# 7_dc_dc_5v_radios.net
KiCad netlist of a schematic drawn in Altium Designer
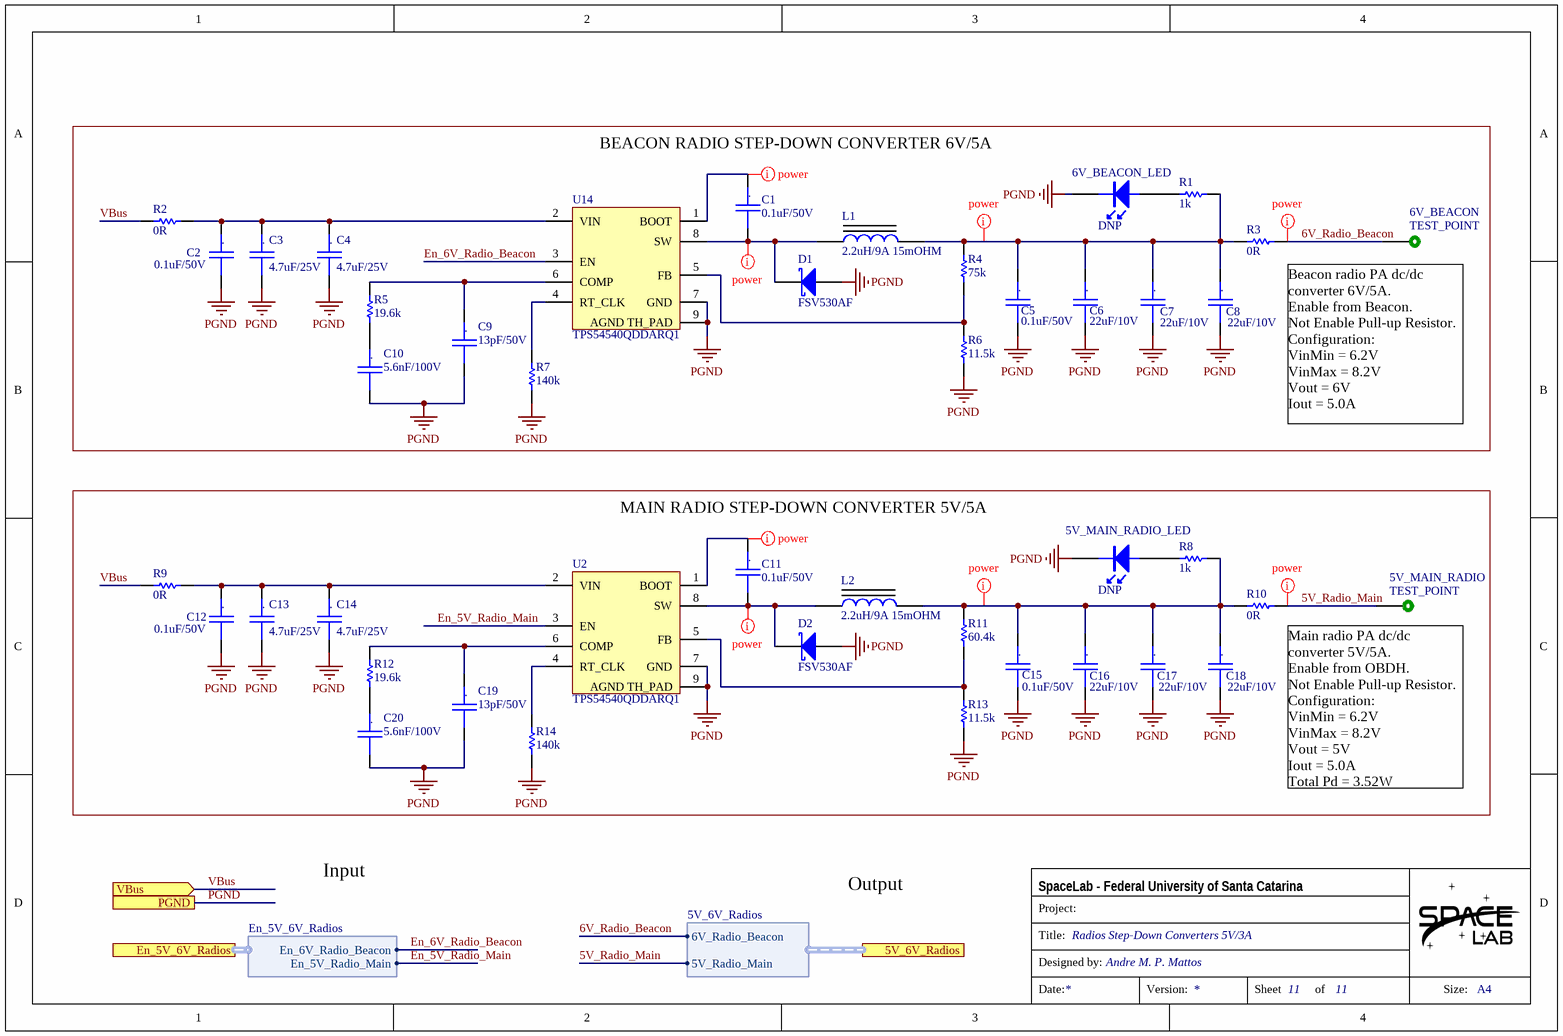
[diagram p0: 7_dc_dc_5v_radios.schdoc]

(export (version "E")
  (design (tool "Eeschema 10.0.6"))
  (components
    (comp (ref "5V_MAIN_RADIO")
      (value "TEST_POINT")
      (footprint "TEST_POINT")
      (description "Test point")
      (libsource (lib "PCB_Project_FlightModel_EPS") (part "TEST_POINT"))
    )
    (comp (ref "5V_MAIN_RADIO_LED")
      (value "DNP")
      (footprint "0603-LED")
      (description "SMD Green LED")
      (fields (field (name "PARTNUMBER") "150060VS75000") (field (name "MANUFACTURER") "Wurth Electronics"))
      (libsource (lib "PCB_Project_FlightModel_EPS") (part "LED/G_0603"))
    )
    (comp (ref "6V_BEACON")
      (value "TEST_POINT")
      (footprint "TEST_POINT")
      (description "Test point")
      (libsource (lib "PCB_Project_FlightModel_EPS") (part "TEST_POINT"))
    )
    (comp (ref "6V_BEACON_LED")
      (value "DNP")
      (footprint "0603-LED")
      (description "SMD Green LED")
      (fields (field (name "PARTNUMBER") "150060VS75000") (field (name "MANUFACTURER") "Wurth Electronics"))
      (libsource (lib "PCB_Project_FlightModel_EPS") (part "LED/G_0603"))
    )
    (comp (ref "C1")
      (value "0.1uF/50V")
      (footprint "CC0805")
      (description "CAP CER 0.1UF 50V 10% X7R 0805")
      (fields (field (name "PARTNUMBER") "CC0805KRX7R9BB104") (field (name "MANUFACTURER") "Yageo"))
      (libsource (lib "PCB_Project_FlightModel_EPS") (part "Cap_Cer_X7R_0.1uF_50V_0805"))
    )
    (comp (ref "C2")
      (value "0.1uF/50V")
      (footprint "CC0805")
      (description "CAP CER 0.1UF 50V 10% X7R 0805")
      (fields (field (name "PARTNUMBER") "CC0805KRX7R9BB104") (field (name "MANUFACTURER") "Yageo"))
      (libsource (lib "PCB_Project_FlightModel_EPS") (part "Cap_Cer_X7R_0.1uF_50V_0805"))
    )
    (comp (ref "C3")
      (value "4.7uF/25V")
      (footprint "CC0805")
      (description "CAP CER 4.7uF 25V 10% X7R 0805")
      (fields (field (name "PARTNUMBER") "CC0805KKX7R8BB475") (field (name "MANUFACTURER") "Yageo"))
      (libsource (lib "PCB_Project_FlightModel_EPS") (part "Cap_Cer_X7R_4.7uF_25V_0805"))
    )
    (comp (ref "C4")
      (value "4.7uF/25V")
      (footprint "CC0805")
      (description "CAP CER 4.7uF 25V 10% X7R 0805")
      (fields (field (name "PARTNUMBER") "CC0805KKX7R8BB475") (field (name "MANUFACTURER") "Yageo"))
      (libsource (lib "PCB_Project_FlightModel_EPS") (part "Cap_Cer_X7R_4.7uF_25V_0805"))
    )
    (comp (ref "C5")
      (value "0.1uF/50V")
      (footprint "CC0805")
      (description "CAP CER 0.1UF 50V 10% X7R 0805")
      (fields (field (name "PARTNUMBER") "CC0805KRX7R9BB104") (field (name "MANUFACTURER") "Yageo"))
      (libsource (lib "PCB_Project_FlightModel_EPS") (part "Cap_Cer_X7R_0.1uF_50V_0805"))
    )
    (comp (ref "C6")
      (value "22uF/10V")
      (footprint "CC1206")
      (description "CAP CER 22uF 10V 10% X7R 1206")
      (fields (field (name "PARTNUMBER") "GRM31CR71A226KE15L") (field (name "MANUFACTURER") "Murata"))
      (libsource (lib "PCB_Project_FlightModel_EPS") (part "Cap_Cer_X7R_22uF_10V_1206"))
    )
    (comp (ref "C7")
      (value "22uF/10V")
      (footprint "CC1206")
      (description "CAP CER 22uF 10V 10% X7R 1206")
      (fields (field (name "PARTNUMBER") "GRM31CR71A226KE15L") (field (name "MANUFACTURER") "Murata"))
      (libsource (lib "PCB_Project_FlightModel_EPS") (part "Cap_Cer_X7R_22uF_10V_1206"))
    )
    (comp (ref "C8")
      (value "22uF/10V")
      (footprint "CC1206")
      (description "CAP CER 22uF 10V 10% X7R 1206")
      (fields (field (name "PARTNUMBER") "GRM31CR71A226KE15L") (field (name "MANUFACTURER") "Murata"))
      (libsource (lib "PCB_Project_FlightModel_EPS") (part "Cap_Cer_X7R_22uF_10V_1206"))
    )
    (comp (ref "C9")
      (value "13pF/50V")
      (footprint "CC0603")
      (description "CAP CER 13PF 50V 0603 NP0")
      (fields (field (name "PARTNUMBER") "C0603C130J5GAC7867") (field (name "MANUFACTURER") "KEMET"))
      (libsource (lib "PCB_Project_FlightModel_EPS") (part "Cap_Cer_C0G_13pF_50V_0603"))
    )
    (comp (ref "C10")
      (value "5.6nF/100V")
      (footprint "CC0603")
      (description "CAP CER 5.6nF 100V 0603")
      (fields (field (name "PARTNUMBER") "C1608C0G2A562J080AE") (field (name "MANUFACTURER") "TDK"))
      (libsource (lib "PCB_Project_FlightModel_EPS") (part "Cap_Cer_C0G_5.6nF_100V_0603"))
    )
    (comp (ref "C11")
      (value "0.1uF/50V")
      (footprint "CC0805")
      (description "CAP CER 0.1UF 50V 10% X7R 0805")
      (fields (field (name "PARTNUMBER") "CC0805KRX7R9BB104") (field (name "MANUFACTURER") "Yageo"))
      (libsource (lib "PCB_Project_FlightModel_EPS") (part "Cap_Cer_X7R_0.1uF_50V_0805"))
    )
    (comp (ref "C12")
      (value "0.1uF/50V")
      (footprint "CC0805")
      (description "CAP CER 0.1UF 50V 10% X7R 0805")
      (fields (field (name "PARTNUMBER") "CC0805KRX7R9BB104") (field (name "MANUFACTURER") "Yageo"))
      (libsource (lib "PCB_Project_FlightModel_EPS") (part "Cap_Cer_X7R_0.1uF_50V_0805"))
    )
    (comp (ref "C13")
      (value "4.7uF/25V")
      (footprint "CC0805")
      (description "CAP CER 4.7uF 25V 10% X7R 0805")
      (fields (field (name "PARTNUMBER") "CC0805KKX7R8BB475") (field (name "MANUFACTURER") "Yageo"))
      (libsource (lib "PCB_Project_FlightModel_EPS") (part "Cap_Cer_X7R_4.7uF_25V_0805"))
    )
    (comp (ref "C14")
      (value "4.7uF/25V")
      (footprint "CC0805")
      (description "CAP CER 4.7uF 25V 10% X7R 0805")
      (fields (field (name "PARTNUMBER") "CC0805KKX7R8BB475") (field (name "MANUFACTURER") "Yageo"))
      (libsource (lib "PCB_Project_FlightModel_EPS") (part "Cap_Cer_X7R_4.7uF_25V_0805"))
    )
    (comp (ref "C15")
      (value "0.1uF/50V")
      (footprint "CC0805")
      (description "CAP CER 0.1UF 50V 10% X7R 0805")
      (fields (field (name "PARTNUMBER") "CC0805KRX7R9BB104") (field (name "MANUFACTURER") "Yageo"))
      (libsource (lib "PCB_Project_FlightModel_EPS") (part "Cap_Cer_X7R_0.1uF_50V_0805"))
    )
    (comp (ref "C16")
      (value "22uF/10V")
      (footprint "CC1206")
      (description "CAP CER 22uF 10V 10% X7R 1206")
      (fields (field (name "PARTNUMBER") "GRM31CR71A226KE15L") (field (name "MANUFACTURER") "Murata"))
      (libsource (lib "PCB_Project_FlightModel_EPS") (part "Cap_Cer_X7R_22uF_10V_1206"))
    )
    (comp (ref "C17")
      (value "22uF/10V")
      (footprint "CC1206")
      (description "CAP CER 22uF 10V 10% X7R 1206")
      (fields (field (name "PARTNUMBER") "GRM31CR71A226KE15L") (field (name "MANUFACTURER") "Murata"))
      (libsource (lib "PCB_Project_FlightModel_EPS") (part "Cap_Cer_X7R_22uF_10V_1206"))
    )
    (comp (ref "C18")
      (value "22uF/10V")
      (footprint "CC1206")
      (description "CAP CER 22uF 10V 10% X7R 1206")
      (fields (field (name "PARTNUMBER") "GRM31CR71A226KE15L") (field (name "MANUFACTURER") "Murata"))
      (libsource (lib "PCB_Project_FlightModel_EPS") (part "Cap_Cer_X7R_22uF_10V_1206"))
    )
    (comp (ref "C19")
      (value "13pF/50V")
      (footprint "CC0603")
      (description "CAP CER 13PF 50V 0603 NP0")
      (fields (field (name "PARTNUMBER") "C0603C130J5GAC7867") (field (name "MANUFACTURER") "KEMET"))
      (libsource (lib "PCB_Project_FlightModel_EPS") (part "Cap_Cer_C0G_13pF_50V_0603"))
    )
    (comp (ref "C20")
      (value "5.6nF/100V")
      (footprint "CC0603")
      (description "CAP CER 5.6nF 100V 0603")
      (fields (field (name "PARTNUMBER") "C1608C0G2A562J080AE") (field (name "MANUFACTURER") "TDK"))
      (libsource (lib "PCB_Project_FlightModel_EPS") (part "Cap_Cer_C0G_5.6nF_100V_0603"))
    )
    (comp (ref "D1")
      (value "FSV530AF")
      (footprint "DO-214AC")
      (description "DIODE SCHOTTKY 30V 5A DO-214AA")
      (fields (field (name "MANUFACTURER") "ON Semiconductor / Fairchild"))
      (libsource (lib "PCB_Project_FlightModel_EPS") (part "DIODE_SCHOTTKY_30V_5A_RB080L-30TE25"))
    )
    (comp (ref "D2")
      (value "FSV530AF")
      (footprint "DO-214AC")
      (description "DIODE SCHOTTKY 30V 5A DO-214AA")
      (fields (field (name "MANUFACTURER") "ON Semiconductor / Fairchild"))
      (libsource (lib "PCB_Project_FlightModel_EPS") (part "DIODE_SCHOTTKY_30V_5A_RB080L-30TE25"))
    )
    (comp (ref "L1")
      (value "2.2uH/9A 15mOHM")
      (footprint "Ind_SRP6540")
      (description "INDUCTOR 2.2UH 9A SMD")
      (fields (field (name "PARTNUMBER") "SRP6540-2R2M") (field (name "MANUFACTURER") "Bourns"))
      (libsource (lib "PCB_Project_FlightModel_EPS") (part "IND_POWER_2.2uH_9A_15mR"))
    )
    (comp (ref "L2")
      (value "2.2uH/9A 15mOHM")
      (footprint "Ind_SRP6540")
      (description "INDUCTOR 2.2UH 9A SMD")
      (fields (field (name "PARTNUMBER") "SRP6540-2R2M") (field (name "MANUFACTURER") "Bourns"))
      (libsource (lib "PCB_Project_FlightModel_EPS") (part "IND_POWER_2.2uH_9A_15mR"))
    )
    (comp (ref "R1")
      (value "1k")
      (footprint "0603")
      (description "RES 1.0K OHM 1/8W 1% 0603")
      (fields (field (name "PARTNUMBER") "MCT06030C1001FP500") (field (name "MANUFACTURER") "Vishay"))
      (libsource (lib "PCB_Project_FlightModel_EPS") (part "R1.0k_1%_1/8W_0603"))
    )
    (comp (ref "R2")
      (value "0R")
      (footprint "1206")
      (description "RES 0.0 OHM 3/4W JUMP 1206")
      (fields
        (field (name "PARTNUMBER") "HCJ1206ZT0R00")
        (field (name "MANUFACTURER") "Stackpole Electronics")
      )
      (libsource (lib "PCB_Project_FlightModel_EPS") (part "R0R_JUMPER_3/4W_1206"))
    )
    (comp (ref "R3")
      (value "0R")
      (footprint "1206")
      (description "RES 0.0 OHM 3/4W JUMP 1206")
      (fields
        (field (name "PARTNUMBER") "HCJ1206ZT0R00")
        (field (name "MANUFACTURER") "Stackpole Electronics")
      )
      (libsource (lib "PCB_Project_FlightModel_EPS") (part "R0R_JUMPER_3/4W_1206"))
    )
    (comp (ref "R4")
      (value "75k")
      (footprint "0805")
      (description "RES 75k OHM 1/8W 1% 0805")
      (fields (field (name "PARTNUMBER") "RMCF0805FT75K0") (field (name "MANUFACTURER") "Panasonic"))
      (libsource (lib "schematics_library_legacy") (part "R75k_1%_1/8W_0805_1"))
    )
    (comp (ref "R5")
      (value "19.6k")
      (footprint "0603")
      (description "RES 19.6k OHM 1/10W 1% 0603")
      (fields (field (name "PARTNUMBER") "ERJ-3EKF1962V") (field (name "MANUFACTURER") "Panasonic"))
      (libsource (lib "PCB_Project_FlightModel_EPS") (part "R19.6k_1%_1/10W_0603"))
    )
    (comp (ref "R6")
      (value "11.5k")
      (footprint "0805")
      (description "RES 11.5k OHM 1/8W 1% 0805")
      (fields (field (name "PARTNUMBER") "AC0805FR-0711K5L") (field (name "MANUFACTURER") "Yageo"))
      (libsource (lib "PCB_Project_FlightModel_EPS") (part "R11.5k_1%_1/8W_0805"))
    )
    (comp (ref "R7")
      (value "140k")
      (footprint "0603")
      (description "RES 140k OHM 1/5W 1% 0603")
      (fields (field (name "PARTNUMBER") "ERJ-P03F1403V") (field (name "MANUFACTURER") "Panasonic"))
      (libsource (lib "PCB_Project_FlightModel_EPS") (part "R140k_1%_1/5W_0603"))
    )
    (comp (ref "R8")
      (value "1k")
      (footprint "0603")
      (description "RES 1.0K OHM 1/8W 1% 0603")
      (fields (field (name "PARTNUMBER") "MCT06030C1001FP500") (field (name "MANUFACTURER") "Vishay"))
      (libsource (lib "PCB_Project_FlightModel_EPS") (part "R1.0k_1%_1/8W_0603"))
    )
    (comp (ref "R9")
      (value "0R")
      (footprint "1206")
      (description "RES 0.0 OHM 3/4W JUMP 1206")
      (fields
        (field (name "PARTNUMBER") "HCJ1206ZT0R00")
        (field (name "MANUFACTURER") "Stackpole Electronics")
      )
      (libsource (lib "PCB_Project_FlightModel_EPS") (part "R0R_JUMPER_3/4W_1206"))
    )
    (comp (ref "R10")
      (value "0R")
      (footprint "1206")
      (description "RES 0.0 OHM 3/4W JUMP 1206")
      (fields
        (field (name "PARTNUMBER") "HCJ1206ZT0R00")
        (field (name "MANUFACTURER") "Stackpole Electronics")
      )
      (libsource (lib "PCB_Project_FlightModel_EPS") (part "R0R_JUMPER_3/4W_1206"))
    )
    (comp (ref "R11")
      (value "60.4k")
      (footprint "0805")
      (description "RES 60.4k OHM 1/8W 1% 0805")
      (fields (field (name "PARTNUMBER") "ERJ-6ENF6042V") (field (name "MANUFACTURER") "Panasonic"))
      (libsource (lib "PCB_Project_FlightModel_EPS") (part "R60.4k_1%_1/8W_0805"))
    )
    (comp (ref "R12")
      (value "19.6k")
      (footprint "0603")
      (description "RES 19.6k OHM 1/10W 1% 0603")
      (fields (field (name "PARTNUMBER") "ERJ-3EKF1962V") (field (name "MANUFACTURER") "Panasonic"))
      (libsource (lib "PCB_Project_FlightModel_EPS") (part "R19.6k_1%_1/10W_0603"))
    )
    (comp (ref "R13")
      (value "11.5k")
      (footprint "0805")
      (description "RES 11.5k OHM 1/8W 1% 0805")
      (fields (field (name "PARTNUMBER") "AC0805FR-0711K5L") (field (name "MANUFACTURER") "Yageo"))
      (libsource (lib "PCB_Project_FlightModel_EPS") (part "R11.5k_1%_1/8W_0805"))
    )
    (comp (ref "R14")
      (value "140k")
      (footprint "0603")
      (description "RES 140k OHM 1/5W 1% 0603")
      (fields (field (name "PARTNUMBER") "ERJ-P03F1403V") (field (name "MANUFACTURER") "Panasonic"))
      (libsource (lib "PCB_Project_FlightModel_EPS") (part "R140k_1%_1/5W_0603"))
    )
    (comp (ref "U2")
      (value "TPS54540QDDARQ1")
      (footprint "SO8 Power PAD")
      (fields (field (name "MANUFACTURER") "Texas Instruments"))
      (libsource (lib "PCB_Project_FlightModel_EPS") (part "TPS54540QDDARQ1"))
    )
    (comp (ref "U14")
      (value "TPS54540QDDARQ1")
      (footprint "SO8 Power PAD")
      (fields (field (name "MANUFACTURER") "Texas Instruments"))
      (libsource (lib "PCB_Project_FlightModel_EPS") (part "TPS54540QDDARQ1"))
    )
  )
  (nets
    (net (code "3") (name "/5V_Radio_Main") (class "Default")
      (node (ref "5V_MAIN_RADIO") (pin "1") (pinfunction "1_1") (pintype "passive"))
      (node (ref "R10") (pin "1") (pinfunction "1_1") (pintype "passive"))
    )
    (net (code "4") (name "/6V_Radio_Beacon") (class "Default")
      (node (ref "6V_BEACON") (pin "1") (pinfunction "1_1") (pintype "passive"))
      (node (ref "R3") (pin "1") (pinfunction "1_1") (pintype "passive"))
    )
    (net (code "5") (name "/En_5V_Radio_Main") (class "Default")
      (node (ref "U2") (pin "3") (pinfunction "EN_3") (pintype "passive"))
    )
    (net (code "6") (name "/En_6V_Radio_Beacon") (class "Default")
      (node (ref "U14") (pin "3") (pinfunction "EN_3") (pintype "passive"))
    )
    (net (code "7") (name "/VBus") (class "Default")
      (node (ref "R2") (pin "2") (pinfunction "2_2") (pintype "passive"))
      (node (ref "R9") (pin "2") (pinfunction "2_2") (pintype "passive"))
    )
    (net (code "10") (name "Net-(5V_MAIN_RADIO_LED-A)") (class "Default")
      (node (ref "5V_MAIN_RADIO_LED") (pin "1") (pinfunction "A_1") (pintype "passive"))
      (node (ref "R8") (pin "2") (pinfunction "2_2") (pintype "passive"))
    )
    (net (code "11") (name "Net-(6V_BEACON_LED-A)") (class "Default")
      (node (ref "6V_BEACON_LED") (pin "1") (pinfunction "A_1") (pintype "passive"))
      (node (ref "R1") (pin "2") (pinfunction "2_2") (pintype "passive"))
    )
    (net (code "12") (name "Net-(C5-Pad1)") (class "Default")
      (node (ref "C5") (pin "1") (pinfunction "1_1") (pintype "passive"))
      (node (ref "C6") (pin "1") (pinfunction "1_1") (pintype "passive"))
      (node (ref "C7") (pin "1") (pinfunction "1_1") (pintype "passive"))
      (node (ref "C8") (pin "1") (pinfunction "1_1") (pintype "passive"))
      (node (ref "L1") (pin "2") (pinfunction "2_2") (pintype "passive"))
      (node (ref "R1") (pin "1") (pinfunction "1_1") (pintype "passive"))
      (node (ref "R3") (pin "2") (pinfunction "2_2") (pintype "passive"))
      (node (ref "R4") (pin "2") (pinfunction "2_2") (pintype "passive"))
    )
    (net (code "13") (name "Net-(C10-Pad1)") (class "Default")
      (node (ref "C10") (pin "1") (pinfunction "1_1") (pintype "passive"))
      (node (ref "R5") (pin "1") (pinfunction "1_1") (pintype "passive"))
    )
    (net (code "14") (name "Net-(C15-Pad1)") (class "Default")
      (node (ref "C15") (pin "1") (pinfunction "1_1") (pintype "passive"))
      (node (ref "C16") (pin "1") (pinfunction "1_1") (pintype "passive"))
      (node (ref "C17") (pin "1") (pinfunction "1_1") (pintype "passive"))
      (node (ref "C18") (pin "1") (pinfunction "1_1") (pintype "passive"))
      (node (ref "L2") (pin "2") (pinfunction "2_2") (pintype "passive"))
      (node (ref "R10") (pin "2") (pinfunction "2_2") (pintype "passive"))
      (node (ref "R11") (pin "2") (pinfunction "2_2") (pintype "passive"))
      (node (ref "R8") (pin "1") (pinfunction "1_1") (pintype "passive"))
    )
    (net (code "15") (name "Net-(C20-Pad1)") (class "Default")
      (node (ref "C20") (pin "1") (pinfunction "1_1") (pintype "passive"))
      (node (ref "R12") (pin "1") (pinfunction "1_1") (pintype "passive"))
    )
    (net (code "16") (name "Net-(D1-K)") (class "Default")
      (node (ref "C1") (pin "2") (pinfunction "2_2") (pintype "passive"))
      (node (ref "D1") (pin "1") (pinfunction "K_1") (pintype "passive"))
      (node (ref "L1") (pin "1") (pinfunction "1_1") (pintype "passive"))
      (node (ref "U14") (pin "8") (pinfunction "SW_8") (pintype "passive"))
    )
    (net (code "17") (name "Net-(D2-K)") (class "Default")
      (node (ref "C11") (pin "2") (pinfunction "2_2") (pintype "passive"))
      (node (ref "D2") (pin "1") (pinfunction "K_1") (pintype "passive"))
      (node (ref "L2") (pin "1") (pinfunction "1_1") (pintype "passive"))
      (node (ref "U2") (pin "8") (pinfunction "SW_8") (pintype "passive"))
    )
    (net (code "18") (name "Net-(U2-BOOT)") (class "Default")
      (node (ref "C11") (pin "1") (pinfunction "1_1") (pintype "passive"))
      (node (ref "U2") (pin "1") (pinfunction "BOOT_1") (pintype "passive"))
    )
    (net (code "19") (name "Net-(U2-COMP)") (class "Default")
      (node (ref "C19") (pin "1") (pinfunction "1_1") (pintype "passive"))
      (node (ref "R12") (pin "2") (pinfunction "2_2") (pintype "passive"))
      (node (ref "U2") (pin "6") (pinfunction "COMP_6") (pintype "passive"))
    )
    (net (code "20") (name "Net-(U2-FB)") (class "Default")
      (node (ref "R11") (pin "1") (pinfunction "1_1") (pintype "passive"))
      (node (ref "R13") (pin "2") (pinfunction "2_2") (pintype "passive"))
      (node (ref "U2") (pin "5") (pinfunction "FB_5") (pintype "passive"))
    )
    (net (code "21") (name "Net-(U2-RT_CLK)") (class "Default")
      (node (ref "R14") (pin "2") (pinfunction "2_2") (pintype "passive"))
      (node (ref "U2") (pin "4") (pinfunction "RT_CLK_4") (pintype "passive"))
    )
    (net (code "22") (name "Net-(U2-VIN)") (class "Default")
      (node (ref "C12") (pin "1") (pinfunction "1_1") (pintype "passive"))
      (node (ref "C13") (pin "1") (pinfunction "1_1") (pintype "passive"))
      (node (ref "C14") (pin "1") (pinfunction "1_1") (pintype "passive"))
      (node (ref "R9") (pin "1") (pinfunction "1_1") (pintype "passive"))
      (node (ref "U2") (pin "2") (pinfunction "VIN_2") (pintype "passive"))
    )
    (net (code "23") (name "Net-(U14-BOOT)") (class "Default")
      (node (ref "C1") (pin "1") (pinfunction "1_1") (pintype "passive"))
      (node (ref "U14") (pin "1") (pinfunction "BOOT_1") (pintype "passive"))
    )
    (net (code "24") (name "Net-(U14-COMP)") (class "Default")
      (node (ref "C9") (pin "1") (pinfunction "1_1") (pintype "passive"))
      (node (ref "R5") (pin "2") (pinfunction "2_2") (pintype "passive"))
      (node (ref "U14") (pin "6") (pinfunction "COMP_6") (pintype "passive"))
    )
    (net (code "25") (name "Net-(U14-FB)") (class "Default")
      (node (ref "R4") (pin "1") (pinfunction "1_1") (pintype "passive"))
      (node (ref "R6") (pin "2") (pinfunction "2_2") (pintype "passive"))
      (node (ref "U14") (pin "5") (pinfunction "FB_5") (pintype "passive"))
    )
    (net (code "26") (name "Net-(U14-RT_CLK)") (class "Default")
      (node (ref "R7") (pin "2") (pinfunction "2_2") (pintype "passive"))
      (node (ref "U14") (pin "4") (pinfunction "RT_CLK_4") (pintype "passive"))
    )
    (net (code "27") (name "Net-(U14-VIN)") (class "Default")
      (node (ref "C2") (pin "1") (pinfunction "1_1") (pintype "passive"))
      (node (ref "C3") (pin "1") (pinfunction "1_1") (pintype "passive"))
      (node (ref "C4") (pin "1") (pinfunction "1_1") (pintype "passive"))
      (node (ref "R2") (pin "1") (pinfunction "1_1") (pintype "passive"))
      (node (ref "U14") (pin "2") (pinfunction "VIN_2") (pintype "passive"))
    )
    (net (code "28") (name "PGND") (class "Default")
      (node (ref "5V_MAIN_RADIO_LED") (pin "2") (pinfunction "K_2") (pintype "passive"))
      (node (ref "6V_BEACON_LED") (pin "2") (pinfunction "K_2") (pintype "passive"))
      (node (ref "C10") (pin "2") (pinfunction "2_2") (pintype "passive"))
      (node (ref "C12") (pin "2") (pinfunction "2_2") (pintype "passive"))
      (node (ref "C13") (pin "2") (pinfunction "2_2") (pintype "passive"))
      (node (ref "C14") (pin "2") (pinfunction "2_2") (pintype "passive"))
      (node (ref "C15") (pin "2") (pinfunction "2_2") (pintype "passive"))
      (node (ref "C16") (pin "2") (pinfunction "2_2") (pintype "passive"))
      (node (ref "C17") (pin "2") (pinfunction "2_2") (pintype "passive"))
      (node (ref "C18") (pin "2") (pinfunction "2_2") (pintype "passive"))
      (node (ref "C19") (pin "2") (pinfunction "2_2") (pintype "passive"))
      (node (ref "C2") (pin "2") (pinfunction "2_2") (pintype "passive"))
      (node (ref "C20") (pin "2") (pinfunction "2_2") (pintype "passive"))
      (node (ref "C3") (pin "2") (pinfunction "2_2") (pintype "passive"))
      (node (ref "C4") (pin "2") (pinfunction "2_2") (pintype "passive"))
      (node (ref "C5") (pin "2") (pinfunction "2_2") (pintype "passive"))
      (node (ref "C6") (pin "2") (pinfunction "2_2") (pintype "passive"))
      (node (ref "C7") (pin "2") (pinfunction "2_2") (pintype "passive"))
      (node (ref "C8") (pin "2") (pinfunction "2_2") (pintype "passive"))
      (node (ref "C9") (pin "2") (pinfunction "2_2") (pintype "passive"))
      (node (ref "D1") (pin "2") (pinfunction "A_2") (pintype "passive"))
      (node (ref "D2") (pin "2") (pinfunction "A_2") (pintype "passive"))
      (node (ref "R13") (pin "1") (pinfunction "1_1") (pintype "passive"))
      (node (ref "R14") (pin "1") (pinfunction "1_1") (pintype "passive"))
      (node (ref "R6") (pin "1") (pinfunction "1_1") (pintype "passive"))
      (node (ref "R7") (pin "1") (pinfunction "1_1") (pintype "passive"))
      (node (ref "U14") (pin "7") (pinfunction "GND_7") (pintype "passive"))
      (node (ref "U14") (pin "9") (pinfunction "AGND_TH_PAD_9") (pintype "passive"))
      (node (ref "U2") (pin "7") (pinfunction "GND_7") (pintype "passive"))
      (node (ref "U2") (pin "9") (pinfunction "AGND_TH_PAD_9") (pintype "passive"))
    )
  )
)
